# Sheet2.net
KiCad netlist of a schematic drawn in Altium Designer
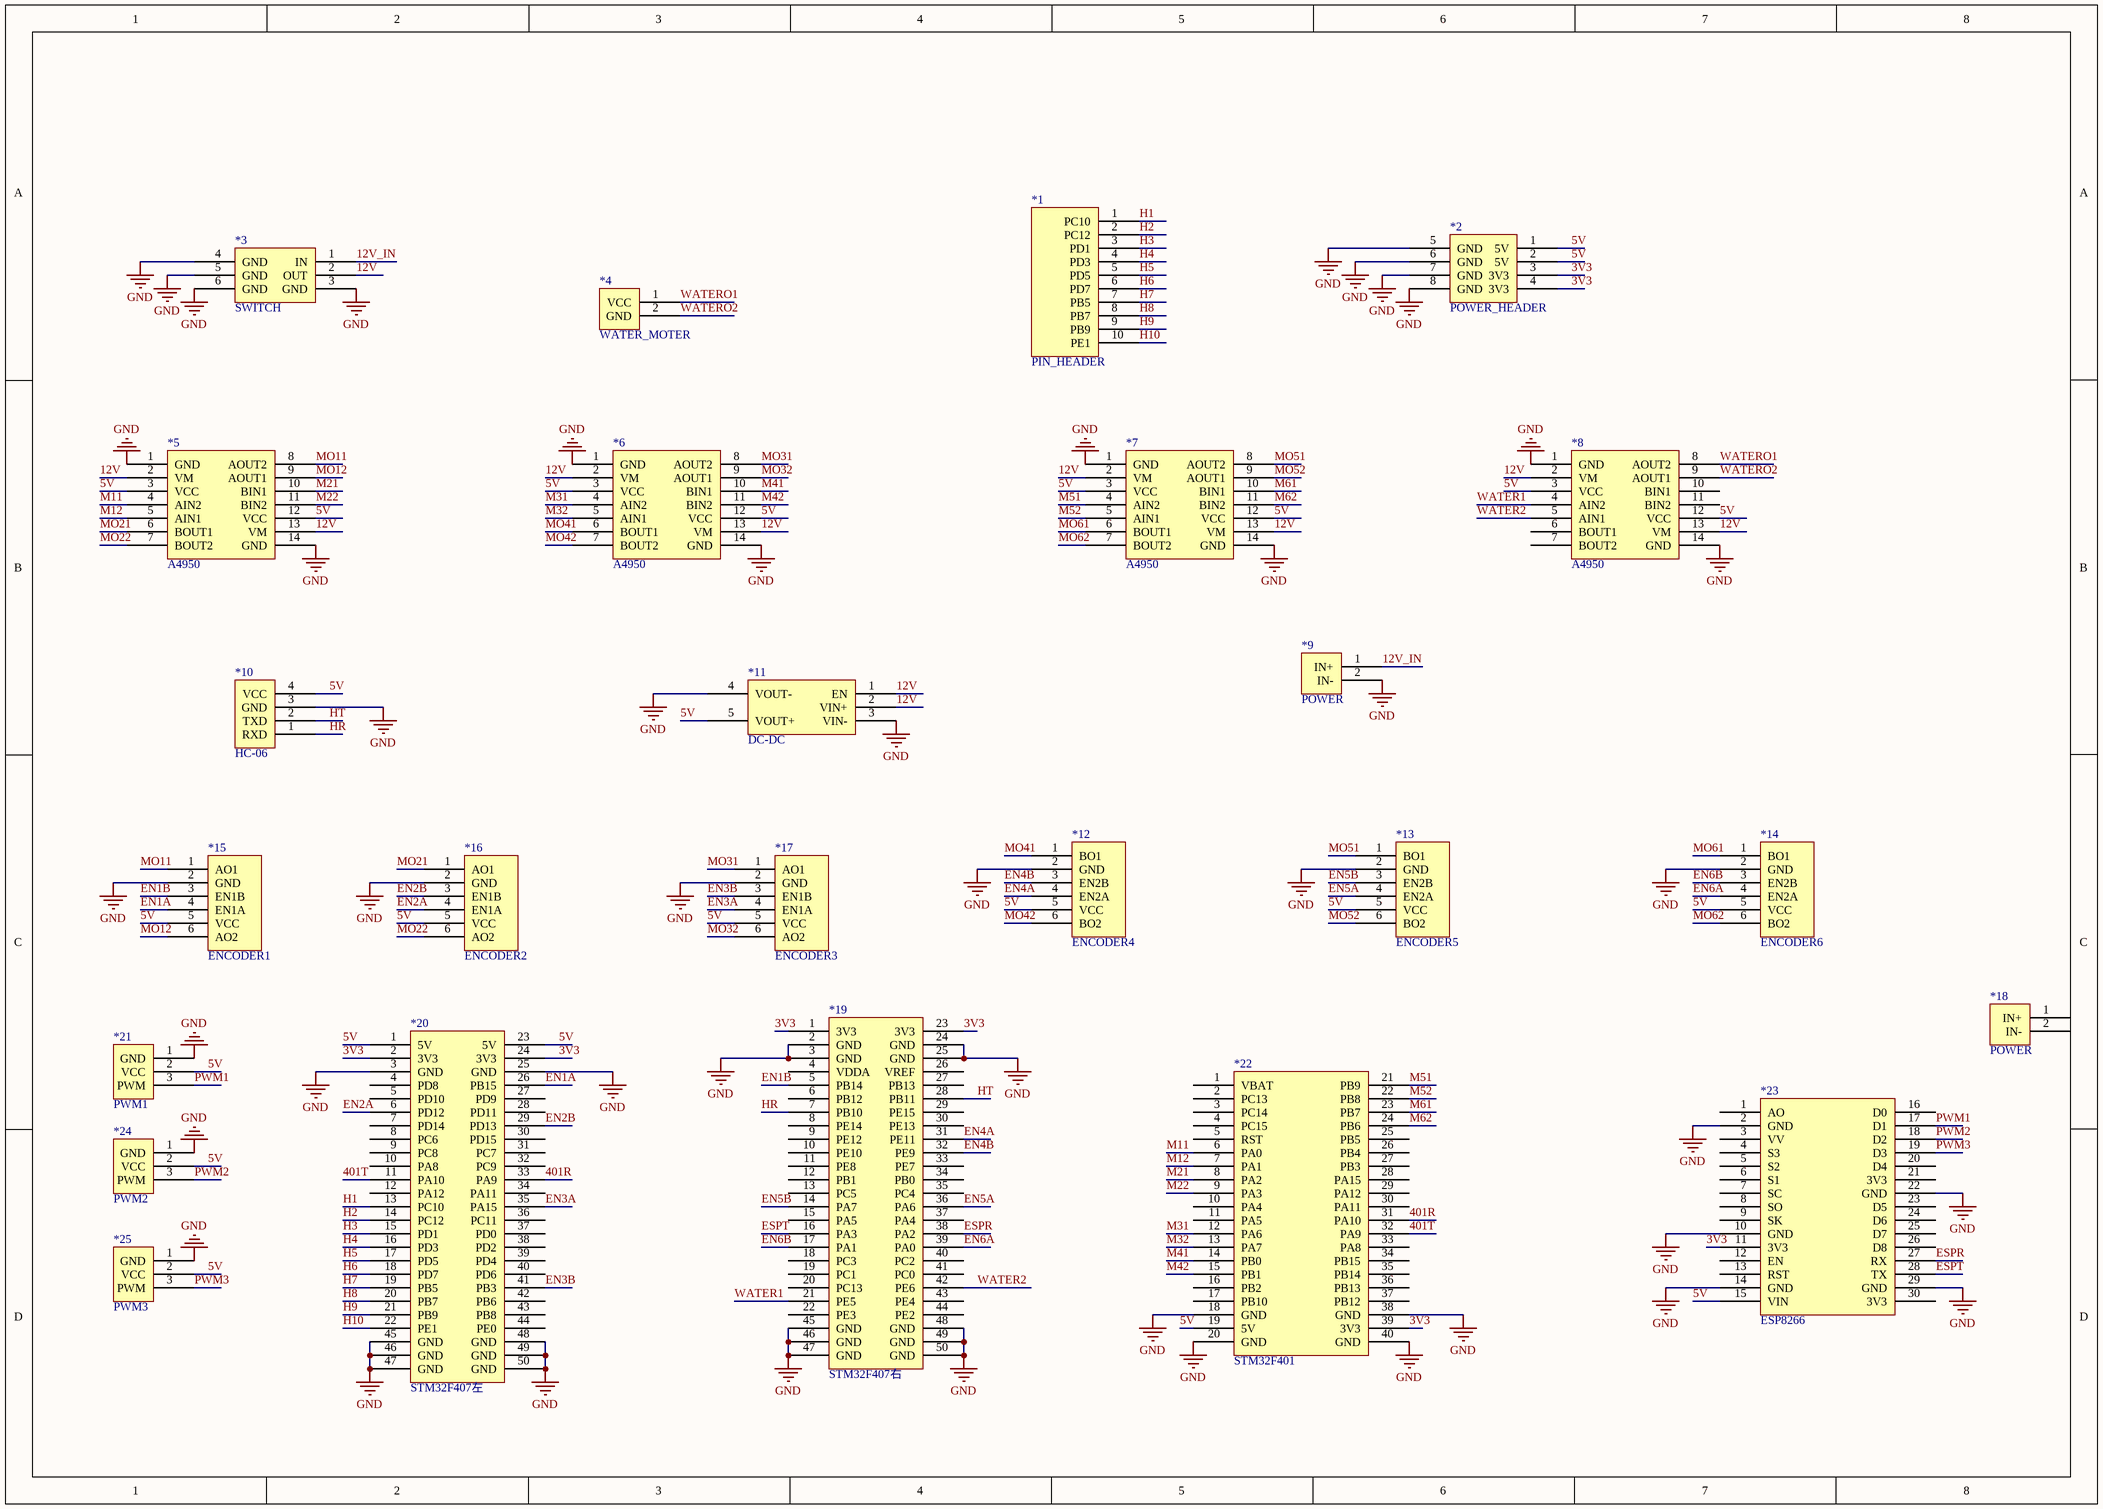
[diagram p0: Sheet2.SchDoc]

(export (version "E")
  (design (tool "Eeschema 10.0.6"))
  (components
    (comp (ref "*1")
      (value "PIN_HEADER")
      (footprint "PIN_HEADER")
      (libsource (lib "Schlib1") (part "PIN_HEADER"))
    )
    (comp (ref "*2")
      (value "POWER_HEADER")
      (footprint "POWER_HEADER")
      (libsource (lib "Schlib1") (part "POWER_HEADER"))
    )
    (comp (ref "*3") (value "SWITCH") (footprint "SIWITCH") (libsource (lib "Schlib1") (part "SWITCH")))
    (comp (ref "*4")
      (value "WATER_MOTER")
      (footprint "WATER_HEADER")
      (libsource (lib "Schlib1") (part "WATER_MOTER"))
    )
    (comp (ref "*5") (value "A4950") (footprint "A4950") (libsource (lib "Schlib1") (part "A4950")))
    (comp (ref "*6") (value "A4950") (footprint "A4950") (libsource (lib "Schlib1") (part "A4950")))
    (comp (ref "*7") (value "A4950") (footprint "A4950") (libsource (lib "Schlib1") (part "A4950")))
    (comp (ref "*8") (value "A4950") (footprint "A4950") (libsource (lib "Schlib1") (part "A4950")))
    (comp (ref "*9") (value "POWER") (footprint "POWER") (libsource (lib "Schlib1") (part "POWER")))
    (comp (ref "*10") (value "HC-06") (footprint "HC-06") (libsource (lib "Schlib1") (part "HC-06")))
    (comp (ref "*11") (value "DC-DC") (footprint "DC-DC") (libsource (lib "Schlib1") (part "DC-DC")))
    (comp (ref "*12") (value "ENCODER4") (footprint "ENCODER2") (libsource (lib "Schlib1") (part "ENCODER4")))
    (comp (ref "*13") (value "ENCODER5") (footprint "ENCODER2") (libsource (lib "Schlib1") (part "ENCODER5")))
    (comp (ref "*14") (value "ENCODER6") (footprint "ENCODER2") (libsource (lib "Schlib1") (part "ENCODER6")))
    (comp (ref "*15") (value "ENCODER1") (footprint "ENCODER1") (libsource (lib "Schlib1") (part "ENCODER1")))
    (comp (ref "*16") (value "ENCODER2") (footprint "ENCODER1") (libsource (lib "Schlib1") (part "ENCODER2")))
    (comp (ref "*17") (value "ENCODER3") (footprint "ENCODER1") (libsource (lib "Schlib1") (part "ENCODER3")))
    (comp (ref "*18") (value "POWER") (footprint "POWER") (libsource (lib "Schlib1") (part "POWER")))
    (comp (ref "*19")
      (value "STM32F407右")
      (footprint "STM32F407左")
      (libsource (lib "Schlib1") (part "STM32F407右"))
    )
    (comp (ref "*20")
      (value "STM32F407左")
      (footprint "STM32F407左")
      (libsource (lib "Schlib1") (part "STM32F407左"))
    )
    (comp (ref "*21") (value "PWM1") (footprint "PWM") (libsource (lib "Schlib1") (part "PWM1")))
    (comp (ref "*22")
      (value "STM32F401")
      (footprint "STM32F401CCU6")
      (libsource (lib "Schlib1") (part "STM32F401"))
    )
    (comp (ref "*23") (value "ESP8266") (footprint "ESP") (libsource (lib "Schlib1") (part "ESP8266")))
    (comp (ref "*24") (value "PWM2") (footprint "PWM") (libsource (lib "Schlib1") (part "PWM2")))
    (comp (ref "*25") (value "PWM3") (footprint "PWM") (libsource (lib "Schlib1") (part "PWM3")))
  )
  (nets
    (net (code "1") (name "/3V3") (class "Default")
      (node (ref "*19") (pin "1") (pinfunction "3V3_1") (pintype "passive"))
      (node (ref "*19") (pin "23") (pinfunction "3V3_23") (pintype "passive"))
      (node (ref "*2") (pin "3") (pinfunction "3V3_3") (pintype "passive"))
      (node (ref "*2") (pin "4") (pinfunction "3V3_4") (pintype "passive"))
      (node (ref "*20") (pin "2") (pinfunction "3V3_2") (pintype "passive"))
      (node (ref "*20") (pin "24") (pinfunction "3V3_24") (pintype "passive"))
      (node (ref "*22") (pin "39") (pinfunction "3V3_39") (pintype "passive"))
      (node (ref "*23") (pin "11") (pinfunction "3V3_11") (pintype "passive"))
    )
    (net (code "2") (name "/5V") (class "Default")
      (node (ref "*10") (pin "4") (pinfunction "VCC_4") (pintype "passive"))
      (node (ref "*11") (pin "5") (pinfunction "VOUT+_5") (pintype "passive"))
      (node (ref "*12") (pin "5") (pinfunction "VCC_5") (pintype "passive"))
      (node (ref "*13") (pin "5") (pinfunction "VCC_5") (pintype "passive"))
      (node (ref "*14") (pin "5") (pinfunction "VCC_5") (pintype "passive"))
      (node (ref "*15") (pin "5") (pinfunction "VCC_5") (pintype "passive"))
      (node (ref "*16") (pin "5") (pinfunction "VCC_5") (pintype "passive"))
      (node (ref "*17") (pin "5") (pinfunction "VCC_5") (pintype "passive"))
      (node (ref "*2") (pin "1") (pinfunction "5V_1") (pintype "passive"))
      (node (ref "*2") (pin "2") (pinfunction "5V_2") (pintype "passive"))
      (node (ref "*20") (pin "1") (pinfunction "5V_1") (pintype "passive"))
      (node (ref "*20") (pin "23") (pinfunction "5V_23") (pintype "passive"))
      (node (ref "*21") (pin "2") (pinfunction "VCC_2") (pintype "passive"))
      (node (ref "*22") (pin "19") (pinfunction "5V_19") (pintype "passive"))
      (node (ref "*23") (pin "15") (pinfunction "VIN_15") (pintype "passive"))
      (node (ref "*24") (pin "2") (pinfunction "VCC_2") (pintype "passive"))
      (node (ref "*25") (pin "2") (pinfunction "VCC_2") (pintype "passive"))
      (node (ref "*5") (pin "12") (pinfunction "VCC_12") (pintype "passive"))
      (node (ref "*5") (pin "3") (pinfunction "VCC_3") (pintype "passive"))
      (node (ref "*6") (pin "12") (pinfunction "VCC_12") (pintype "passive"))
      (node (ref "*6") (pin "3") (pinfunction "VCC_3") (pintype "passive"))
      (node (ref "*7") (pin "12") (pinfunction "VCC_12") (pintype "passive"))
      (node (ref "*7") (pin "3") (pinfunction "VCC_3") (pintype "passive"))
      (node (ref "*8") (pin "12") (pinfunction "VCC_12") (pintype "passive"))
      (node (ref "*8") (pin "3") (pinfunction "VCC_3") (pintype "passive"))
    )
    (net (code "3") (name "/12V") (class "Default")
      (node (ref "*11") (pin "1") (pinfunction "EN_1") (pintype "passive"))
      (node (ref "*11") (pin "2") (pinfunction "VIN+_2") (pintype "passive"))
      (node (ref "*3") (pin "2") (pinfunction "OUT_2") (pintype "passive"))
      (node (ref "*5") (pin "13") (pinfunction "VM_13") (pintype "passive"))
      (node (ref "*5") (pin "2") (pinfunction "VM_2") (pintype "passive"))
      (node (ref "*6") (pin "13") (pinfunction "VM_13") (pintype "passive"))
      (node (ref "*6") (pin "2") (pinfunction "VM_2") (pintype "passive"))
      (node (ref "*7") (pin "13") (pinfunction "VM_13") (pintype "passive"))
      (node (ref "*7") (pin "2") (pinfunction "VM_2") (pintype "passive"))
      (node (ref "*8") (pin "13") (pinfunction "VM_13") (pintype "passive"))
      (node (ref "*8") (pin "2") (pinfunction "VM_2") (pintype "passive"))
    )
    (net (code "4") (name "/12V_IN") (class "Default")
      (node (ref "*3") (pin "1") (pinfunction "IN_1") (pintype "passive"))
      (node (ref "*9") (pin "1") (pinfunction "IN+_1") (pintype "passive"))
    )
    (net (code "5") (name "/401R") (class "Default")
      (node (ref "*20") (pin "33") (pinfunction "PA9_33") (pintype "passive"))
      (node (ref "*22") (pin "31") (pinfunction "PA10_31") (pintype "passive"))
    )
    (net (code "6") (name "/401T") (class "Default")
      (node (ref "*20") (pin "11") (pinfunction "PA10_11") (pintype "passive"))
      (node (ref "*22") (pin "32") (pinfunction "PA9_32") (pintype "passive"))
    )
    (net (code "7") (name "/EN1A") (class "Default")
      (node (ref "*15") (pin "4") (pinfunction "EN1A_4") (pintype "passive"))
      (node (ref "*20") (pin "26") (pinfunction "PB15_26") (pintype "passive"))
    )
    (net (code "8") (name "/EN1B") (class "Default")
      (node (ref "*15") (pin "3") (pinfunction "EN1B_3") (pintype "passive"))
      (node (ref "*19") (pin "5") (pinfunction "PB14_5") (pintype "passive"))
    )
    (net (code "9") (name "/EN2A") (class "Default")
      (node (ref "*16") (pin "4") (pinfunction "EN1A_4") (pintype "passive"))
      (node (ref "*20") (pin "6") (pinfunction "PD12_6") (pintype "passive"))
    )
    (net (code "10") (name "/EN2B") (class "Default")
      (node (ref "*16") (pin "3") (pinfunction "EN1B_3") (pintype "passive"))
      (node (ref "*20") (pin "29") (pinfunction "PD13_29") (pintype "passive"))
    )
    (net (code "11") (name "/EN3A") (class "Default")
      (node (ref "*17") (pin "4") (pinfunction "EN1A_4") (pintype "passive"))
      (node (ref "*20") (pin "35") (pinfunction "PA15_35") (pintype "passive"))
    )
    (net (code "12") (name "/EN3B") (class "Default")
      (node (ref "*17") (pin "3") (pinfunction "EN1B_3") (pintype "passive"))
      (node (ref "*20") (pin "41") (pinfunction "PB3_41") (pintype "passive"))
    )
    (net (code "13") (name "/EN4A") (class "Default")
      (node (ref "*12") (pin "4") (pinfunction "EN2A_4") (pintype "passive"))
      (node (ref "*19") (pin "31") (pinfunction "PE11_31") (pintype "passive"))
    )
    (net (code "14") (name "/EN4B") (class "Default")
      (node (ref "*12") (pin "3") (pinfunction "EN2B_3") (pintype "passive"))
      (node (ref "*19") (pin "32") (pinfunction "PE9_32") (pintype "passive"))
    )
    (net (code "15") (name "/EN5A") (class "Default")
      (node (ref "*13") (pin "4") (pinfunction "EN2A_4") (pintype "passive"))
      (node (ref "*19") (pin "36") (pinfunction "PA6_36") (pintype "passive"))
    )
    (net (code "16") (name "/EN5B") (class "Default")
      (node (ref "*13") (pin "3") (pinfunction "EN2B_3") (pintype "passive"))
      (node (ref "*19") (pin "14") (pinfunction "PA7_14") (pintype "passive"))
    )
    (net (code "17") (name "/EN6A") (class "Default")
      (node (ref "*14") (pin "4") (pinfunction "EN2A_4") (pintype "passive"))
      (node (ref "*19") (pin "39") (pinfunction "PA0_39") (pintype "passive"))
    )
    (net (code "18") (name "/EN6B") (class "Default")
      (node (ref "*14") (pin "3") (pinfunction "EN2B_3") (pintype "passive"))
      (node (ref "*19") (pin "17") (pinfunction "PA1_17") (pintype "passive"))
    )
    (net (code "19") (name "/ESPR") (class "Default")
      (node (ref "*19") (pin "38") (pinfunction "PA2_38") (pintype "passive"))
      (node (ref "*23") (pin "27") (pinfunction "RX_27") (pintype "passive"))
    )
    (net (code "20") (name "/ESPT") (class "Default")
      (node (ref "*19") (pin "16") (pinfunction "PA3_16") (pintype "passive"))
      (node (ref "*23") (pin "28") (pinfunction "TX_28") (pintype "passive"))
    )
    (net (code "21") (name "/H1") (class "Default")
      (node (ref "*1") (pin "1") (pinfunction "PC10_1") (pintype "passive"))
      (node (ref "*20") (pin "13") (pinfunction "PC10_13") (pintype "passive"))
    )
    (net (code "22") (name "/H2") (class "Default")
      (node (ref "*1") (pin "2") (pinfunction "PC12_2") (pintype "passive"))
      (node (ref "*20") (pin "14") (pinfunction "PC12_14") (pintype "passive"))
    )
    (net (code "23") (name "/H3") (class "Default")
      (node (ref "*1") (pin "3") (pinfunction "PD1_3") (pintype "passive"))
      (node (ref "*20") (pin "15") (pinfunction "PD1_15") (pintype "passive"))
    )
    (net (code "24") (name "/H4") (class "Default")
      (node (ref "*1") (pin "4") (pinfunction "PD3_4") (pintype "passive"))
      (node (ref "*20") (pin "16") (pinfunction "PD3_16") (pintype "passive"))
    )
    (net (code "25") (name "/H5") (class "Default")
      (node (ref "*1") (pin "5") (pinfunction "PD5_5") (pintype "passive"))
      (node (ref "*20") (pin "17") (pinfunction "PD5_17") (pintype "passive"))
    )
    (net (code "26") (name "/H6") (class "Default")
      (node (ref "*1") (pin "6") (pinfunction "PD7_6") (pintype "passive"))
      (node (ref "*20") (pin "18") (pinfunction "PD7_18") (pintype "passive"))
    )
    (net (code "27") (name "/H7") (class "Default")
      (node (ref "*1") (pin "7") (pinfunction "PB5_7") (pintype "passive"))
      (node (ref "*20") (pin "19") (pinfunction "PB5_19") (pintype "passive"))
    )
    (net (code "28") (name "/H8") (class "Default")
      (node (ref "*1") (pin "8") (pinfunction "PB7_8") (pintype "passive"))
      (node (ref "*20") (pin "20") (pinfunction "PB7_20") (pintype "passive"))
    )
    (net (code "29") (name "/H9") (class "Default")
      (node (ref "*1") (pin "9") (pinfunction "PB9_9") (pintype "passive"))
      (node (ref "*20") (pin "21") (pinfunction "PB9_21") (pintype "passive"))
    )
    (net (code "30") (name "/H10") (class "Default")
      (node (ref "*1") (pin "10") (pinfunction "PE1_10") (pintype "passive"))
      (node (ref "*20") (pin "22") (pinfunction "PE1_22") (pintype "passive"))
    )
    (net (code "31") (name "/HR") (class "Default")
      (node (ref "*10") (pin "1") (pinfunction "RXD_1") (pintype "passive"))
      (node (ref "*19") (pin "7") (pinfunction "PB10_7") (pintype "passive"))
    )
    (net (code "32") (name "/HT") (class "Default")
      (node (ref "*10") (pin "2") (pinfunction "TXD_2") (pintype "passive"))
      (node (ref "*19") (pin "28") (pinfunction "PB11_28") (pintype "passive"))
    )
    (net (code "33") (name "/M11") (class "Default")
      (node (ref "*22") (pin "6") (pinfunction "PA0_6") (pintype "passive"))
      (node (ref "*5") (pin "4") (pinfunction "AIN2_4") (pintype "passive"))
    )
    (net (code "34") (name "/M12") (class "Default")
      (node (ref "*22") (pin "7") (pinfunction "PA1_7") (pintype "passive"))
      (node (ref "*5") (pin "5") (pinfunction "AIN1_5") (pintype "passive"))
    )
    (net (code "35") (name "/M21") (class "Default")
      (node (ref "*22") (pin "8") (pinfunction "PA2_8") (pintype "passive"))
      (node (ref "*5") (pin "10") (pinfunction "BIN1_10") (pintype "passive"))
    )
    (net (code "36") (name "/M22") (class "Default")
      (node (ref "*22") (pin "9") (pinfunction "PA3_9") (pintype "passive"))
      (node (ref "*5") (pin "11") (pinfunction "BIN2_11") (pintype "passive"))
    )
    (net (code "37") (name "/M31") (class "Default")
      (node (ref "*22") (pin "12") (pinfunction "PA6_12") (pintype "passive"))
      (node (ref "*6") (pin "4") (pinfunction "AIN2_4") (pintype "passive"))
    )
    (net (code "38") (name "/M32") (class "Default")
      (node (ref "*22") (pin "13") (pinfunction "PA7_13") (pintype "passive"))
      (node (ref "*6") (pin "5") (pinfunction "AIN1_5") (pintype "passive"))
    )
    (net (code "39") (name "/M41") (class "Default")
      (node (ref "*22") (pin "14") (pinfunction "PB0_14") (pintype "passive"))
      (node (ref "*6") (pin "10") (pinfunction "BIN1_10") (pintype "passive"))
    )
    (net (code "40") (name "/M42") (class "Default")
      (node (ref "*22") (pin "15") (pinfunction "PB1_15") (pintype "passive"))
      (node (ref "*6") (pin "11") (pinfunction "BIN2_11") (pintype "passive"))
    )
    (net (code "41") (name "/M51") (class "Default")
      (node (ref "*22") (pin "21") (pinfunction "PB9_21") (pintype "passive"))
      (node (ref "*7") (pin "4") (pinfunction "AIN2_4") (pintype "passive"))
    )
    (net (code "42") (name "/M52") (class "Default")
      (node (ref "*22") (pin "22") (pinfunction "PB8_22") (pintype "passive"))
      (node (ref "*7") (pin "5") (pinfunction "AIN1_5") (pintype "passive"))
    )
    (net (code "43") (name "/M61") (class "Default")
      (node (ref "*22") (pin "23") (pinfunction "PB7_23") (pintype "passive"))
      (node (ref "*7") (pin "10") (pinfunction "BIN1_10") (pintype "passive"))
    )
    (net (code "44") (name "/M62") (class "Default")
      (node (ref "*22") (pin "24") (pinfunction "PB6_24") (pintype "passive"))
      (node (ref "*7") (pin "11") (pinfunction "BIN2_11") (pintype "passive"))
    )
    (net (code "45") (name "/MO11") (class "Default")
      (node (ref "*15") (pin "1") (pinfunction "AO1_1") (pintype "passive"))
      (node (ref "*5") (pin "8") (pinfunction "AOUT2_8") (pintype "passive"))
    )
    (net (code "46") (name "/MO12") (class "Default")
      (node (ref "*15") (pin "6") (pinfunction "AO2_6") (pintype "passive"))
      (node (ref "*5") (pin "9") (pinfunction "AOUT1_9") (pintype "passive"))
    )
    (net (code "47") (name "/MO21") (class "Default")
      (node (ref "*16") (pin "1") (pinfunction "AO1_1") (pintype "passive"))
      (node (ref "*5") (pin "6") (pinfunction "BOUT1_6") (pintype "passive"))
    )
    (net (code "48") (name "/MO22") (class "Default")
      (node (ref "*16") (pin "6") (pinfunction "AO2_6") (pintype "passive"))
      (node (ref "*5") (pin "7") (pinfunction "BOUT2_7") (pintype "passive"))
    )
    (net (code "49") (name "/MO31") (class "Default")
      (node (ref "*17") (pin "1") (pinfunction "AO1_1") (pintype "passive"))
      (node (ref "*6") (pin "8") (pinfunction "AOUT2_8") (pintype "passive"))
    )
    (net (code "50") (name "/MO32") (class "Default")
      (node (ref "*17") (pin "6") (pinfunction "AO2_6") (pintype "passive"))
      (node (ref "*6") (pin "9") (pinfunction "AOUT1_9") (pintype "passive"))
    )
    (net (code "51") (name "/MO41") (class "Default")
      (node (ref "*12") (pin "1") (pinfunction "BO1_1") (pintype "passive"))
      (node (ref "*6") (pin "6") (pinfunction "BOUT1_6") (pintype "passive"))
    )
    (net (code "52") (name "/MO42") (class "Default")
      (node (ref "*12") (pin "6") (pinfunction "BO2_6") (pintype "passive"))
      (node (ref "*6") (pin "7") (pinfunction "BOUT2_7") (pintype "passive"))
    )
    (net (code "53") (name "/MO51") (class "Default")
      (node (ref "*13") (pin "1") (pinfunction "BO1_1") (pintype "passive"))
      (node (ref "*7") (pin "8") (pinfunction "AOUT2_8") (pintype "passive"))
    )
    (net (code "54") (name "/MO52") (class "Default")
      (node (ref "*13") (pin "6") (pinfunction "BO2_6") (pintype "passive"))
      (node (ref "*7") (pin "9") (pinfunction "AOUT1_9") (pintype "passive"))
    )
    (net (code "55") (name "/MO61") (class "Default")
      (node (ref "*14") (pin "1") (pinfunction "BO1_1") (pintype "passive"))
      (node (ref "*7") (pin "6") (pinfunction "BOUT1_6") (pintype "passive"))
    )
    (net (code "56") (name "/MO62") (class "Default")
      (node (ref "*14") (pin "6") (pinfunction "BO2_6") (pintype "passive"))
      (node (ref "*7") (pin "7") (pinfunction "BOUT2_7") (pintype "passive"))
    )
    (net (code "57") (name "/PWM1") (class "Default")
      (node (ref "*21") (pin "3") (pinfunction "PWM_3") (pintype "passive"))
      (node (ref "*23") (pin "17") (pinfunction "D1_17") (pintype "passive"))
    )
    (net (code "58") (name "/PWM2") (class "Default")
      (node (ref "*23") (pin "18") (pinfunction "D2_18") (pintype "passive"))
      (node (ref "*24") (pin "3") (pinfunction "PWM_3") (pintype "passive"))
    )
    (net (code "59") (name "/PWM3") (class "Default")
      (node (ref "*23") (pin "19") (pinfunction "D3_19") (pintype "passive"))
      (node (ref "*25") (pin "3") (pinfunction "PWM_3") (pintype "passive"))
    )
    (net (code "60") (name "/WATER1") (class "Default")
      (node (ref "*19") (pin "21") (pinfunction "PE5_21") (pintype "passive"))
      (node (ref "*8") (pin "4") (pinfunction "AIN2_4") (pintype "passive"))
    )
    (net (code "61") (name "/WATER2") (class "Default")
      (node (ref "*19") (pin "42") (pinfunction "PE6_42") (pintype "passive"))
      (node (ref "*8") (pin "5") (pinfunction "AIN1_5") (pintype "passive"))
    )
    (net (code "62") (name "/WATERO1") (class "Default")
      (node (ref "*4") (pin "1") (pinfunction "VCC_1") (pintype "passive"))
      (node (ref "*8") (pin "8") (pinfunction "AOUT2_8") (pintype "passive"))
    )
    (net (code "63") (name "/WATERO2") (class "Default")
      (node (ref "*4") (pin "2") (pinfunction "GND_2") (pintype "passive"))
      (node (ref "*8") (pin "9") (pinfunction "AOUT1_9") (pintype "passive"))
    )
    (net (code "64") (name "GND") (class "Default")
      (node (ref "*10") (pin "3") (pinfunction "GND_3") (pintype "passive"))
      (node (ref "*11") (pin "3") (pinfunction "VIN-_3") (pintype "passive"))
      (node (ref "*11") (pin "4") (pinfunction "VOUT-_4") (pintype "passive"))
      (node (ref "*12") (pin "2") (pinfunction "GND_2") (pintype "passive"))
      (node (ref "*13") (pin "2") (pinfunction "GND_2") (pintype "passive"))
      (node (ref "*14") (pin "2") (pinfunction "GND_2") (pintype "passive"))
      (node (ref "*15") (pin "2") (pinfunction "GND_2") (pintype "passive"))
      (node (ref "*16") (pin "2") (pinfunction "GND_2") (pintype "passive"))
      (node (ref "*17") (pin "2") (pinfunction "GND_2") (pintype "passive"))
      (node (ref "*19") (pin "2") (pinfunction "GND_2") (pintype "passive"))
      (node (ref "*19") (pin "24") (pinfunction "GND_24") (pintype "passive"))
      (node (ref "*19") (pin "25") (pinfunction "GND_25") (pintype "passive"))
      (node (ref "*19") (pin "3") (pinfunction "GND_3") (pintype "passive"))
      (node (ref "*19") (pin "45") (pinfunction "GND_45") (pintype "passive"))
      (node (ref "*19") (pin "46") (pinfunction "GND_46") (pintype "passive"))
      (node (ref "*19") (pin "47") (pinfunction "GND_47") (pintype "passive"))
      (node (ref "*19") (pin "48") (pinfunction "GND_48") (pintype "passive"))
      (node (ref "*19") (pin "49") (pinfunction "GND_49") (pintype "passive"))
      (node (ref "*19") (pin "50") (pinfunction "GND_50") (pintype "passive"))
      (node (ref "*2") (pin "5") (pinfunction "GND_5") (pintype "passive"))
      (node (ref "*2") (pin "6") (pinfunction "GND_6") (pintype "passive"))
      (node (ref "*2") (pin "7") (pinfunction "GND_7") (pintype "passive"))
      (node (ref "*2") (pin "8") (pinfunction "GND_8") (pintype "passive"))
      (node (ref "*20") (pin "25") (pinfunction "GND_25") (pintype "passive"))
      (node (ref "*20") (pin "3") (pinfunction "GND_3") (pintype "passive"))
      (node (ref "*20") (pin "45") (pinfunction "GND_45") (pintype "passive"))
      (node (ref "*20") (pin "46") (pinfunction "GND_46") (pintype "passive"))
      (node (ref "*20") (pin "47") (pinfunction "GND_47") (pintype "passive"))
      (node (ref "*20") (pin "48") (pinfunction "GND_48") (pintype "passive"))
      (node (ref "*20") (pin "49") (pinfunction "GND_49") (pintype "passive"))
      (node (ref "*20") (pin "50") (pinfunction "GND_50") (pintype "passive"))
      (node (ref "*21") (pin "1") (pinfunction "GND_1") (pintype "passive"))
      (node (ref "*22") (pin "18") (pinfunction "GND_18") (pintype "passive"))
      (node (ref "*22") (pin "20") (pinfunction "GND_20") (pintype "passive"))
      (node (ref "*22") (pin "38") (pinfunction "GND_38") (pintype "passive"))
      (node (ref "*22") (pin "40") (pinfunction "GND_40") (pintype "passive"))
      (node (ref "*23") (pin "10") (pinfunction "GND_10") (pintype "passive"))
      (node (ref "*23") (pin "14") (pinfunction "GND_14") (pintype "passive"))
      (node (ref "*23") (pin "2") (pinfunction "GND_2") (pintype "passive"))
      (node (ref "*23") (pin "22") (pinfunction "GND_22") (pintype "passive"))
      (node (ref "*23") (pin "29") (pinfunction "GND_29") (pintype "passive"))
      (node (ref "*24") (pin "1") (pinfunction "GND_1") (pintype "passive"))
      (node (ref "*25") (pin "1") (pinfunction "GND_1") (pintype "passive"))
      (node (ref "*3") (pin "3") (pinfunction "GND_3") (pintype "passive"))
      (node (ref "*3") (pin "4") (pinfunction "GND_4") (pintype "passive"))
      (node (ref "*3") (pin "5") (pinfunction "GND_5") (pintype "passive"))
      (node (ref "*3") (pin "6") (pinfunction "GND_6") (pintype "passive"))
      (node (ref "*5") (pin "1") (pinfunction "GND_1") (pintype "passive"))
      (node (ref "*5") (pin "14") (pinfunction "GND_14") (pintype "passive"))
      (node (ref "*6") (pin "1") (pinfunction "GND_1") (pintype "passive"))
      (node (ref "*6") (pin "14") (pinfunction "GND_14") (pintype "passive"))
      (node (ref "*7") (pin "1") (pinfunction "GND_1") (pintype "passive"))
      (node (ref "*7") (pin "14") (pinfunction "GND_14") (pintype "passive"))
      (node (ref "*8") (pin "1") (pinfunction "GND_1") (pintype "passive"))
      (node (ref "*8") (pin "14") (pinfunction "GND_14") (pintype "passive"))
      (node (ref "*9") (pin "2") (pinfunction "IN-_2") (pintype "passive"))
    )
    (net (code "65") (name "unconnected-(*8-BIN1-Pad10)") (class "Default")
      (node (ref "*8") (pin "10") (pinfunction "BIN1_10") (pintype "passive"))
    )
    (net (code "66") (name "unconnected-(*8-BIN2-Pad11)") (class "Default")
      (node (ref "*8") (pin "11") (pinfunction "BIN2_11") (pintype "passive"))
    )
    (net (code "67") (name "unconnected-(*8-BOUT1-Pad6)") (class "Default")
      (node (ref "*8") (pin "6") (pinfunction "BOUT1_6") (pintype "passive"))
    )
    (net (code "68") (name "unconnected-(*8-BOUT2-Pad7)") (class "Default")
      (node (ref "*8") (pin "7") (pinfunction "BOUT2_7") (pintype "passive"))
    )
    (net (code "69") (name "unconnected-(*18-IN+-Pad1)") (class "Default")
      (node (ref "*18") (pin "1") (pinfunction "IN+_1") (pintype "passive"))
    )
    (net (code "70") (name "unconnected-(*18-IN--Pad2)") (class "Default")
      (node (ref "*18") (pin "2") (pinfunction "IN-_2") (pintype "passive"))
    )
    (net (code "71") (name "unconnected-(*19-PA4-Pad37)") (class "Default")
      (node (ref "*19") (pin "37") (pinfunction "PA4_37") (pintype "passive"))
    )
    (net (code "72") (name "unconnected-(*19-PA5-Pad15)") (class "Default")
      (node (ref "*19") (pin "15") (pinfunction "PA5_15") (pintype "passive"))
    )
    (net (code "73") (name "unconnected-(*19-PB0-Pad34)") (class "Default")
      (node (ref "*19") (pin "34") (pinfunction "PB0_34") (pintype "passive"))
    )
    (net (code "74") (name "unconnected-(*19-PB1-Pad12)") (class "Default")
      (node (ref "*19") (pin "12") (pinfunction "PB1_12") (pintype "passive"))
    )
    (net (code "75") (name "unconnected-(*19-PB12-Pad6)") (class "Default")
      (node (ref "*19") (pin "6") (pinfunction "PB12_6") (pintype "passive"))
    )
    (net (code "76") (name "unconnected-(*19-PB13-Pad27)") (class "Default")
      (node (ref "*19") (pin "27") (pinfunction "PB13_27") (pintype "passive"))
    )
    (net (code "77") (name "unconnected-(*19-PC0-Pad41)") (class "Default")
      (node (ref "*19") (pin "41") (pinfunction "PC0_41") (pintype "passive"))
    )
    (net (code "78") (name "unconnected-(*19-PC1-Pad19)") (class "Default")
      (node (ref "*19") (pin "19") (pinfunction "PC1_19") (pintype "passive"))
    )
    (net (code "79") (name "unconnected-(*19-PC2-Pad40)") (class "Default")
      (node (ref "*19") (pin "40") (pinfunction "PC2_40") (pintype "passive"))
    )
    (net (code "80") (name "unconnected-(*19-PC3-Pad18)") (class "Default")
      (node (ref "*19") (pin "18") (pinfunction "PC3_18") (pintype "passive"))
    )
    (net (code "81") (name "unconnected-(*19-PC4-Pad35)") (class "Default")
      (node (ref "*19") (pin "35") (pinfunction "PC4_35") (pintype "passive"))
    )
    (net (code "82") (name "unconnected-(*19-PC5-Pad13)") (class "Default")
      (node (ref "*19") (pin "13") (pinfunction "PC5_13") (pintype "passive"))
    )
    (net (code "83") (name "unconnected-(*19-PC13-Pad20)") (class "Default")
      (node (ref "*19") (pin "20") (pinfunction "PC13_20") (pintype "passive"))
    )
    (net (code "84") (name "unconnected-(*19-PE2-Pad44)") (class "Default")
      (node (ref "*19") (pin "44") (pinfunction "PE2_44") (pintype "passive"))
    )
    (net (code "85") (name "unconnected-(*19-PE3-Pad22)") (class "Default")
      (node (ref "*19") (pin "22") (pinfunction "PE3_22") (pintype "passive"))
    )
    (net (code "86") (name "unconnected-(*19-PE4-Pad43)") (class "Default")
      (node (ref "*19") (pin "43") (pinfunction "PE4_43") (pintype "passive"))
    )
    (net (code "87") (name "unconnected-(*19-PE7-Pad33)") (class "Default")
      (node (ref "*19") (pin "33") (pinfunction "PE7_33") (pintype "passive"))
    )
    (net (code "88") (name "unconnected-(*19-PE8-Pad11)") (class "Default")
      (node (ref "*19") (pin "11") (pinfunction "PE8_11") (pintype "passive"))
    )
    (net (code "89") (name "unconnected-(*19-PE10-Pad10)") (class "Default")
      (node (ref "*19") (pin "10") (pinfunction "PE10_10") (pintype "passive"))
    )
    (net (code "90") (name "unconnected-(*19-PE12-Pad9)") (class "Default")
      (node (ref "*19") (pin "9") (pinfunction "PE12_9") (pintype "passive"))
    )
    (net (code "91") (name "unconnected-(*19-PE13-Pad30)") (class "Default")
      (node (ref "*19") (pin "30") (pinfunction "PE13_30") (pintype "passive"))
    )
    (net (code "92") (name "unconnected-(*19-PE14-Pad8)") (class "Default")
      (node (ref "*19") (pin "8") (pinfunction "PE14_8") (pintype "passive"))
    )
    (net (code "93") (name "unconnected-(*19-PE15-Pad29)") (class "Default")
      (node (ref "*19") (pin "29") (pinfunction "PE15_29") (pintype "passive"))
    )
    (net (code "94") (name "unconnected-(*19-VDDA-Pad4)") (class "Default")
      (node (ref "*19") (pin "4") (pinfunction "VDDA_4") (pintype "passive"))
    )
    (net (code "95") (name "unconnected-(*19-VREF-Pad26)") (class "Default")
      (node (ref "*19") (pin "26") (pinfunction "VREF_26") (pintype "passive"))
    )
    (net (code "96") (name "unconnected-(*20-PA8-Pad10)") (class "Default")
      (node (ref "*20") (pin "10") (pinfunction "PA8_10") (pintype "passive"))
    )
    (net (code "97") (name "unconnected-(*20-PA11-Pad34)") (class "Default")
      (node (ref "*20") (pin "34") (pinfunction "PA11_34") (pintype "passive"))
    )
    (net (code "98") (name "unconnected-(*20-PA12-Pad12)") (class "Default")
      (node (ref "*20") (pin "12") (pinfunction "PA12_12") (pintype "passive"))
    )
    (net (code "99") (name "unconnected-(*20-PB6-Pad42)") (class "Default")
      (node (ref "*20") (pin "42") (pinfunction "PB6_42") (pintype "passive"))
    )
    (net (code "100") (name "unconnected-(*20-PB8-Pad43)") (class "Default")
      (node (ref "*20") (pin "43") (pinfunction "PB8_43") (pintype "passive"))
    )
    (net (code "101") (name "unconnected-(*20-PC6-Pad8)") (class "Default")
      (node (ref "*20") (pin "8") (pinfunction "PC6_8") (pintype "passive"))
    )
    (net (code "102") (name "unconnected-(*20-PC7-Pad31)") (class "Default")
      (node (ref "*20") (pin "31") (pinfunction "PC7_31") (pintype "passive"))
    )
    (net (code "103") (name "unconnected-(*20-PC8-Pad9)") (class "Default")
      (node (ref "*20") (pin "9") (pinfunction "PC8_9") (pintype "passive"))
    )
    (net (code "104") (name "unconnected-(*20-PC9-Pad32)") (class "Default")
      (node (ref "*20") (pin "32") (pinfunction "PC9_32") (pintype "passive"))
    )
    (net (code "105") (name "unconnected-(*20-PC11-Pad36)") (class "Default")
      (node (ref "*20") (pin "36") (pinfunction "PC11_36") (pintype "passive"))
    )
    (net (code "106") (name "unconnected-(*20-PD0-Pad37)") (class "Default")
      (node (ref "*20") (pin "37") (pinfunction "PD0_37") (pintype "passive"))
    )
    (net (code "107") (name "unconnected-(*20-PD2-Pad38)") (class "Default")
      (node (ref "*20") (pin "38") (pinfunction "PD2_38") (pintype "passive"))
    )
    (net (code "108") (name "unconnected-(*20-PD4-Pad39)") (class "Default")
      (node (ref "*20") (pin "39") (pinfunction "PD4_39") (pintype "passive"))
    )
    (net (code "109") (name "unconnected-(*20-PD6-Pad40)") (class "Default")
      (node (ref "*20") (pin "40") (pinfunction "PD6_40") (pintype "passive"))
    )
    (net (code "110") (name "unconnected-(*20-PD8-Pad4)") (class "Default")
      (node (ref "*20") (pin "4") (pinfunction "PD8_4") (pintype "passive"))
    )
    (net (code "111") (name "unconnected-(*20-PD9-Pad27)") (class "Default")
      (node (ref "*20") (pin "27") (pinfunction "PD9_27") (pintype "passive"))
    )
    (net (code "112") (name "unconnected-(*20-PD10-Pad5)") (class "Default")
      (node (ref "*20") (pin "5") (pinfunction "PD10_5") (pintype "passive"))
    )
    (net (code "113") (name "unconnected-(*20-PD11-Pad28)") (class "Default")
      (node (ref "*20") (pin "28") (pinfunction "PD11_28") (pintype "passive"))
    )
    (net (code "114") (name "unconnected-(*20-PD14-Pad7)") (class "Default")
      (node (ref "*20") (pin "7") (pinfunction "PD14_7") (pintype "passive"))
    )
    (net (code "115") (name "unconnected-(*20-PD15-Pad30)") (class "Default")
      (node (ref "*20") (pin "30") (pinfunction "PD15_30") (pintype "passive"))
    )
    (net (code "116") (name "unconnected-(*20-PE0-Pad44)") (class "Default")
      (node (ref "*20") (pin "44") (pinfunction "PE0_44") (pintype "passive"))
    )
    (net (code "117") (name "unconnected-(*22-PA4-Pad10)") (class "Default")
      (node (ref "*22") (pin "10") (pinfunction "PA4_10") (pintype "passive"))
    )
    (net (code "118") (name "unconnected-(*22-PA5-Pad11)") (class "Default")
      (node (ref "*22") (pin "11") (pinfunction "PA5_11") (pintype "passive"))
    )
    (net (code "119") (name "unconnected-(*22-PA8-Pad33)") (class "Default")
      (node (ref "*22") (pin "33") (pinfunction "PA8_33") (pintype "passive"))
    )
    (net (code "120") (name "unconnected-(*22-PA11-Pad30)") (class "Default")
      (node (ref "*22") (pin "30") (pinfunction "PA11_30") (pintype "passive"))
    )
    (net (code "121") (name "unconnected-(*22-PA12-Pad29)") (class "Default")
      (node (ref "*22") (pin "29") (pinfunction "PA12_29") (pintype "passive"))
    )
    (net (code "122") (name "unconnected-(*22-PA15-Pad28)") (class "Default")
      (node (ref "*22") (pin "28") (pinfunction "PA15_28") (pintype "passive"))
    )
    (net (code "123") (name "unconnected-(*22-PB2-Pad16)") (class "Default")
      (node (ref "*22") (pin "16") (pinfunction "PB2_16") (pintype "passive"))
    )
    (net (code "124") (name "unconnected-(*22-PB3-Pad27)") (class "Default")
      (node (ref "*22") (pin "27") (pinfunction "PB3_27") (pintype "passive"))
    )
    (net (code "125") (name "unconnected-(*22-PB4-Pad26)") (class "Default")
      (node (ref "*22") (pin "26") (pinfunction "PB4_26") (pintype "passive"))
    )
    (net (code "126") (name "unconnected-(*22-PB5-Pad25)") (class "Default")
      (node (ref "*22") (pin "25") (pinfunction "PB5_25") (pintype "passive"))
    )
    (net (code "127") (name "unconnected-(*22-PB10-Pad17)") (class "Default")
      (node (ref "*22") (pin "17") (pinfunction "PB10_17") (pintype "passive"))
    )
    (net (code "128") (name "unconnected-(*22-PB12-Pad37)") (class "Default")
      (node (ref "*22") (pin "37") (pinfunction "PB12_37") (pintype "passive"))
    )
    (net (code "129") (name "unconnected-(*22-PB13-Pad36)") (class "Default")
      (node (ref "*22") (pin "36") (pinfunction "PB13_36") (pintype "passive"))
    )
    (net (code "130") (name "unconnected-(*22-PB14-Pad35)") (class "Default")
      (node (ref "*22") (pin "35") (pinfunction "PB14_35") (pintype "passive"))
    )
    (net (code "131") (name "unconnected-(*22-PB15-Pad34)") (class "Default")
      (node (ref "*22") (pin "34") (pinfunction "PB15_34") (pintype "passive"))
    )
    (net (code "132") (name "unconnected-(*22-PC13-Pad2)") (class "Default")
      (node (ref "*22") (pin "2") (pinfunction "PC13_2") (pintype "passive"))
    )
    (net (code "133") (name "unconnected-(*22-PC14-Pad3)") (class "Default")
      (node (ref "*22") (pin "3") (pinfunction "PC14_3") (pintype "passive"))
    )
    (net (code "134") (name "unconnected-(*22-PC15-Pad4)") (class "Default")
      (node (ref "*22") (pin "4") (pinfunction "PC15_4") (pintype "passive"))
    )
    (net (code "135") (name "unconnected-(*22-RST-Pad5)") (class "Default")
      (node (ref "*22") (pin "5") (pinfunction "RST_5") (pintype "passive"))
    )
    (net (code "136") (name "unconnected-(*22-VBAT-Pad1)") (class "Default")
      (node (ref "*22") (pin "1") (pinfunction "VBAT_1") (pintype "passive"))
    )
    (net (code "137") (name "unconnected-(*23-3V3-Pad21)") (class "Default")
      (node (ref "*23") (pin "21") (pinfunction "3V3_21") (pintype "passive"))
    )
    (net (code "138") (name "unconnected-(*23-3V3-Pad30)") (class "Default")
      (node (ref "*23") (pin "30") (pinfunction "3V3_30") (pintype "passive"))
    )
    (net (code "139") (name "unconnected-(*23-AO-Pad1)") (class "Default")
      (node (ref "*23") (pin "1") (pinfunction "AO_1") (pintype "passive"))
    )
    (net (code "140") (name "unconnected-(*23-D0-Pad16)") (class "Default")
      (node (ref "*23") (pin "16") (pinfunction "D0_16") (pintype "passive"))
    )
    (net (code "141") (name "unconnected-(*23-D4-Pad20)") (class "Default")
      (node (ref "*23") (pin "20") (pinfunction "D4_20") (pintype "passive"))
    )
    (net (code "142") (name "unconnected-(*23-D5-Pad23)") (class "Default")
      (node (ref "*23") (pin "23") (pinfunction "D5_23") (pintype "passive"))
    )
    (net (code "143") (name "unconnected-(*23-D6-Pad24)") (class "Default")
      (node (ref "*23") (pin "24") (pinfunction "D6_24") (pintype "passive"))
    )
    (net (code "144") (name "unconnected-(*23-D7-Pad25)") (class "Default")
      (node (ref "*23") (pin "25") (pinfunction "D7_25") (pintype "passive"))
    )
    (net (code "145") (name "unconnected-(*23-D8-Pad26)") (class "Default")
      (node (ref "*23") (pin "26") (pinfunction "D8_26") (pintype "passive"))
    )
    (net (code "146") (name "unconnected-(*23-EN-Pad12)") (class "Default")
      (node (ref "*23") (pin "12") (pinfunction "EN_12") (pintype "passive"))
    )
    (net (code "147") (name "unconnected-(*23-RST-Pad13)") (class "Default")
      (node (ref "*23") (pin "13") (pinfunction "RST_13") (pintype "passive"))
    )
    (net (code "148") (name "unconnected-(*23-S1-Pad6)") (class "Default")
      (node (ref "*23") (pin "6") (pinfunction "S1_6") (pintype "passive"))
    )
    (net (code "149") (name "unconnected-(*23-S2-Pad5)") (class "Default")
      (node (ref "*23") (pin "5") (pinfunction "S2_5") (pintype "passive"))
    )
    (net (code "150") (name "unconnected-(*23-S3-Pad4)") (class "Default")
      (node (ref "*23") (pin "4") (pinfunction "S3_4") (pintype "passive"))
    )
    (net (code "151") (name "unconnected-(*23-SC-Pad7)") (class "Default")
      (node (ref "*23") (pin "7") (pinfunction "SC_7") (pintype "passive"))
    )
    (net (code "152") (name "unconnected-(*23-SK-Pad9)") (class "Default")
      (node (ref "*23") (pin "9") (pinfunction "SK_9") (pintype "passive"))
    )
    (net (code "153") (name "unconnected-(*23-SO-Pad8)") (class "Default")
      (node (ref "*23") (pin "8") (pinfunction "SO_8") (pintype "passive"))
    )
    (net (code "154") (name "unconnected-(*23-VV-Pad3)") (class "Default")
      (node (ref "*23") (pin "3") (pinfunction "VV_3") (pintype "passive"))
    )
  )
)
